# level-shifter-v0_1.net
KiCad netlist of a schematic drawn in EAGLE
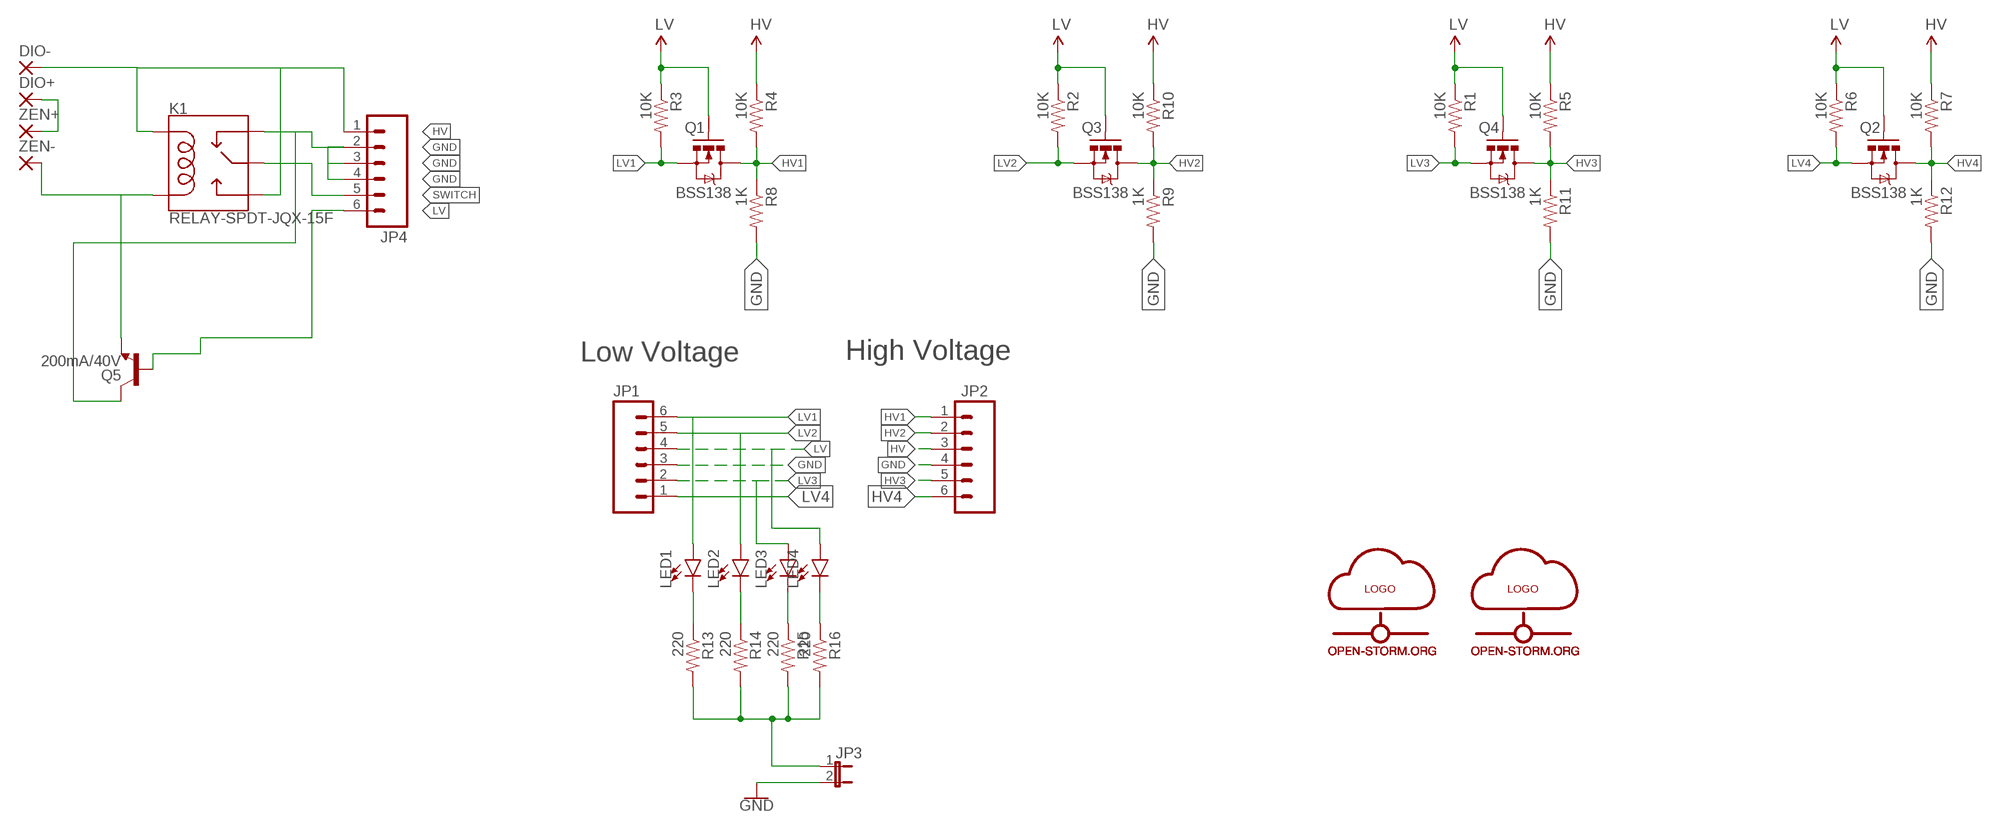
[diagram p0: schematic, sheet 1]

(export (version "E")
  (design (tool "Eeschema 10.0.6"))
  (components
    (comp (ref "DIO+")
      (value "2,15/1,0")
      (footprint "eagle-import:2,15_1,0")
      (libsource (lib "eagle-import") (part "2,15/1,0"))
    )
    (comp (ref "DIO-")
      (value "2,15/1,0")
      (footprint "eagle-import:2,15_1,0")
      (libsource (lib "eagle-import") (part "2,15/1,0"))
    )
    (comp (ref "JP1")
      (value "M06SIP")
      (footprint "eagle-import:1X06")
      (libsource (lib "eagle-import") (part "M06SIP"))
    )
    (comp (ref "JP2")
      (value "M06SIP")
      (footprint "eagle-import:1X06")
      (libsource (lib "eagle-import") (part "M06SIP"))
    )
    (comp (ref "JP3")
      (value "JUMPER-2PTH")
      (footprint "eagle-import:1X02")
      (libsource (lib "eagle-import") (part "JUMPER-2PTH"))
    )
    (comp (ref "JP4")
      (value "M06SIP")
      (footprint "eagle-import:1X06")
      (libsource (lib "eagle-import") (part "M06SIP"))
    )
    (comp (ref "K1")
      (value "RELAY-SPDT-JQX-15F")
      (footprint "eagle-import:RELAY-T90")
      (libsource (lib "eagle-import") (part "RELAY-SPDT-JQX-15F"))
    )
    (comp (ref "LED1")
      (value "LED5MM")
      (footprint "eagle-import:LED_5MM")
      (libsource (lib "eagle-import") (part "LED5MM"))
    )
    (comp (ref "LED2")
      (value "LED5MM")
      (footprint "eagle-import:LED_5MM")
      (libsource (lib "eagle-import") (part "LED5MM"))
    )
    (comp (ref "LED3")
      (value "LED5MM")
      (footprint "eagle-import:LED_5MM")
      (libsource (lib "eagle-import") (part "LED5MM"))
    )
    (comp (ref "LED4")
      (value "LED5MM")
      (footprint "eagle-import:LED_5MM")
      (libsource (lib "eagle-import") (part "LED5MM"))
    )
    (comp (ref "Q1")
      (value "BSS138")
      (footprint "eagle-import:TO-92")
      (libsource (lib "eagle-import") (part "MOSFET-NCHANNELPTH"))
    )
    (comp (ref "Q2")
      (value "BSS138")
      (footprint "eagle-import:TO-92")
      (libsource (lib "eagle-import") (part "MOSFET-NCHANNELPTH"))
    )
    (comp (ref "Q3")
      (value "BSS138")
      (footprint "eagle-import:TO-92")
      (libsource (lib "eagle-import") (part "MOSFET-NCHANNELPTH"))
    )
    (comp (ref "Q4")
      (value "BSS138")
      (footprint "eagle-import:TO-92")
      (libsource (lib "eagle-import") (part "MOSFET-NCHANNELPTH"))
    )
    (comp (ref "Q5")
      (value "200mA/40V")
      (footprint "eagle-import:TO-92")
      (libsource (lib "eagle-import") (part "TRANS_NPN-2N3904"))
    )
    (comp (ref "R1")
      (value "10K")
      (footprint "eagle-import:AXIAL-0.4")
      (libsource (lib "eagle-import") (part "RESISTORPTH-1/4W"))
    )
    (comp (ref "R2")
      (value "10K")
      (footprint "eagle-import:AXIAL-0.4")
      (libsource (lib "eagle-import") (part "RESISTORPTH-1/4W"))
    )
    (comp (ref "R3")
      (value "10K")
      (footprint "eagle-import:AXIAL-0.4")
      (libsource (lib "eagle-import") (part "RESISTORPTH-1/4W"))
    )
    (comp (ref "R4")
      (value "10K")
      (footprint "eagle-import:AXIAL-0.4")
      (libsource (lib "eagle-import") (part "RESISTORPTH-1/4W"))
    )
    (comp (ref "R5")
      (value "10K")
      (footprint "eagle-import:AXIAL-0.4")
      (libsource (lib "eagle-import") (part "RESISTORPTH-1/4W"))
    )
    (comp (ref "R6")
      (value "10K")
      (footprint "eagle-import:AXIAL-0.4")
      (libsource (lib "eagle-import") (part "RESISTORPTH-1/4W"))
    )
    (comp (ref "R7")
      (value "10K")
      (footprint "eagle-import:AXIAL-0.4")
      (libsource (lib "eagle-import") (part "RESISTORPTH-1/4W"))
    )
    (comp (ref "R8")
      (value "1K")
      (footprint "eagle-import:AXIAL-0.4")
      (libsource (lib "eagle-import") (part "RESISTORPTH-1/4W"))
    )
    (comp (ref "R9")
      (value "1K")
      (footprint "eagle-import:AXIAL-0.4")
      (libsource (lib "eagle-import") (part "RESISTORPTH-1/4W"))
    )
    (comp (ref "R10")
      (value "10K")
      (footprint "eagle-import:AXIAL-0.4")
      (libsource (lib "eagle-import") (part "RESISTORPTH-1/4W"))
    )
    (comp (ref "R11")
      (value "1K")
      (footprint "eagle-import:AXIAL-0.4")
      (libsource (lib "eagle-import") (part "RESISTORPTH-1/4W"))
    )
    (comp (ref "R12")
      (value "1K")
      (footprint "eagle-import:AXIAL-0.4")
      (libsource (lib "eagle-import") (part "RESISTORPTH-1/4W"))
    )
    (comp (ref "R13")
      (value "220")
      (footprint "eagle-import:AXIAL-0.4")
      (libsource (lib "eagle-import") (part "RESISTORPTH-1/4W"))
    )
    (comp (ref "R14")
      (value "220")
      (footprint "eagle-import:AXIAL-0.4")
      (libsource (lib "eagle-import") (part "RESISTORPTH-1/4W"))
    )
    (comp (ref "R15")
      (value "220")
      (footprint "eagle-import:AXIAL-0.4")
      (libsource (lib "eagle-import") (part "RESISTORPTH-1/4W"))
    )
    (comp (ref "R16")
      (value "220")
      (footprint "eagle-import:AXIAL-0.4")
      (libsource (lib "eagle-import") (part "RESISTORPTH-1/4W"))
    )
    (comp (ref "U$1")
      (value "OPEN-STORM-LOGO")
      (footprint "eagle-import:OPEN-STORM-LOGO")
      (libsource (lib "eagle-import") (part "OPEN-STORM-LOGO"))
    )
    (comp (ref "U$2")
      (value "OPEN-STORM-LOGO-SMALL")
      (footprint "eagle-import:OPEN-STORM-LOGO-SMALL")
      (libsource (lib "eagle-import") (part "OPEN-STORM-LOGO-SMALL"))
    )
    (comp (ref "ZEN+")
      (value "2,15/1,0")
      (footprint "eagle-import:2,15_1,0")
      (libsource (lib "eagle-import") (part "2,15/1,0"))
    )
    (comp (ref "ZEN-")
      (value "2,15/1,0")
      (footprint "eagle-import:2,15_1,0")
      (libsource (lib "eagle-import") (part "2,15/1,0"))
    )
  )
  (nets
    (net (code "1") (name "GND") (class "Default")
      (node (ref "JP1") (pin "3") (pinfunction "3_3") (pintype "passive"))
      (node (ref "JP2") (pin "4") (pinfunction "4_4") (pintype "passive"))
      (node (ref "JP3") (pin "2") (pinfunction "2_2") (pintype "passive"))
      (node (ref "JP4") (pin "2") (pinfunction "2_2") (pintype "passive"))
      (node (ref "JP4") (pin "3") (pinfunction "3_3") (pintype "passive"))
      (node (ref "JP4") (pin "4") (pinfunction "4_4") (pintype "passive"))
      (node (ref "K1") (pin "NC") (pinfunction "NC_NC") (pintype "bidirectional"))
      (node (ref "Q5") (pin "3") (pinfunction "C_3") (pintype "passive"))
      (node (ref "R11") (pin "P$2") (pinfunction "2_P$2") (pintype "passive"))
      (node (ref "R12") (pin "P$2") (pinfunction "2_P$2") (pintype "passive"))
      (node (ref "R8") (pin "P$2") (pinfunction "2_P$2") (pintype "passive"))
      (node (ref "R9") (pin "P$2") (pinfunction "2_P$2") (pintype "passive"))
    )
    (net (code "2") (name "HV") (class "Default")
      (node (ref "DIO-") (pin "1") (pinfunction "P_1") (pintype "passive"))
      (node (ref "JP2") (pin "3") (pinfunction "3_3") (pintype "passive"))
      (node (ref "JP4") (pin "1") (pinfunction "1_1") (pintype "passive"))
      (node (ref "K1") (pin "COIL1") (pinfunction "COIL1_COIL1") (pintype "bidirectional"))
      (node (ref "K1") (pin "NO") (pinfunction "NO_NO") (pintype "bidirectional"))
      (node (ref "R10") (pin "P$1") (pinfunction "1_P$1") (pintype "passive"))
      (node (ref "R4") (pin "P$1") (pinfunction "1_P$1") (pintype "passive"))
      (node (ref "R5") (pin "P$1") (pinfunction "1_P$1") (pintype "passive"))
      (node (ref "R7") (pin "P$1") (pinfunction "1_P$1") (pintype "passive"))
    )
    (net (code "3") (name "HV1") (class "Default")
      (node (ref "JP2") (pin "1") (pinfunction "1_1") (pintype "passive"))
      (node (ref "Q1") (pin "1") (pinfunction "D_1") (pintype "passive"))
      (node (ref "R4") (pin "P$2") (pinfunction "2_P$2") (pintype "passive"))
      (node (ref "R8") (pin "P$1") (pinfunction "1_P$1") (pintype "passive"))
    )
    (net (code "4") (name "HV2") (class "Default")
      (node (ref "JP2") (pin "2") (pinfunction "2_2") (pintype "passive"))
      (node (ref "Q3") (pin "1") (pinfunction "D_1") (pintype "passive"))
      (node (ref "R10") (pin "P$2") (pinfunction "2_P$2") (pintype "passive"))
      (node (ref "R9") (pin "P$1") (pinfunction "1_P$1") (pintype "passive"))
    )
    (net (code "5") (name "HV3") (class "Default")
      (node (ref "JP2") (pin "5") (pinfunction "5_5") (pintype "passive"))
      (node (ref "Q4") (pin "1") (pinfunction "D_1") (pintype "passive"))
      (node (ref "R11") (pin "P$1") (pinfunction "1_P$1") (pintype "passive"))
      (node (ref "R5") (pin "P$2") (pinfunction "2_P$2") (pintype "passive"))
    )
    (net (code "6") (name "HV4") (class "Default")
      (node (ref "JP2") (pin "6") (pinfunction "6_6") (pintype "passive"))
      (node (ref "Q2") (pin "1") (pinfunction "D_1") (pintype "passive"))
      (node (ref "R12") (pin "P$1") (pinfunction "1_P$1") (pintype "passive"))
      (node (ref "R7") (pin "P$2") (pinfunction "2_P$2") (pintype "passive"))
    )
    (net (code "7") (name "LV") (class "Default")
      (node (ref "JP1") (pin "4") (pinfunction "4_4") (pintype "passive"))
      (node (ref "JP4") (pin "6") (pinfunction "6_6") (pintype "passive"))
      (node (ref "LED4") (pin "A") (pinfunction "A_A") (pintype "passive"))
      (node (ref "Q1") (pin "3") (pinfunction "G_3") (pintype "passive"))
      (node (ref "Q2") (pin "3") (pinfunction "G_3") (pintype "passive"))
      (node (ref "Q3") (pin "3") (pinfunction "G_3") (pintype "passive"))
      (node (ref "Q4") (pin "3") (pinfunction "G_3") (pintype "passive"))
      (node (ref "Q5") (pin "2") (pinfunction "B_2") (pintype "passive"))
      (node (ref "R1") (pin "P$1") (pinfunction "1_P$1") (pintype "passive"))
      (node (ref "R2") (pin "P$1") (pinfunction "1_P$1") (pintype "passive"))
      (node (ref "R3") (pin "P$1") (pinfunction "1_P$1") (pintype "passive"))
      (node (ref "R6") (pin "P$1") (pinfunction "1_P$1") (pintype "passive"))
    )
    (net (code "8") (name "LV1") (class "Default")
      (node (ref "JP1") (pin "6") (pinfunction "6_6") (pintype "passive"))
      (node (ref "LED1") (pin "A") (pinfunction "A_A") (pintype "passive"))
      (node (ref "Q1") (pin "2") (pinfunction "S_2") (pintype "passive"))
      (node (ref "R3") (pin "P$2") (pinfunction "2_P$2") (pintype "passive"))
    )
    (net (code "9") (name "LV2") (class "Default")
      (node (ref "JP1") (pin "5") (pinfunction "5_5") (pintype "passive"))
      (node (ref "LED2") (pin "A") (pinfunction "A_A") (pintype "passive"))
      (node (ref "Q3") (pin "2") (pinfunction "S_2") (pintype "passive"))
      (node (ref "R2") (pin "P$2") (pinfunction "2_P$2") (pintype "passive"))
    )
    (net (code "10") (name "LV3") (class "Default")
      (node (ref "JP1") (pin "2") (pinfunction "2_2") (pintype "passive"))
      (node (ref "LED3") (pin "A") (pinfunction "A_A") (pintype "passive"))
      (node (ref "Q4") (pin "2") (pinfunction "S_2") (pintype "passive"))
      (node (ref "R1") (pin "P$2") (pinfunction "2_P$2") (pintype "passive"))
    )
    (net (code "11") (name "LV4") (class "Default")
      (node (ref "JP1") (pin "1") (pinfunction "1_1") (pintype "passive"))
      (node (ref "Q2") (pin "2") (pinfunction "S_2") (pintype "passive"))
      (node (ref "R6") (pin "P$2") (pinfunction "2_P$2") (pintype "passive"))
    )
    (net (code "12") (name "Net-(DIO+-P)") (class "Default")
      (node (ref "DIO+") (pin "1") (pinfunction "P_1") (pintype "passive"))
      (node (ref "ZEN+") (pin "1") (pinfunction "P_1") (pintype "passive"))
    )
    (net (code "13") (name "Net-(LED1-C)") (class "Default")
      (node (ref "LED1") (pin "K") (pinfunction "C_K") (pintype "passive"))
      (node (ref "R13") (pin "P$1") (pinfunction "1_P$1") (pintype "passive"))
    )
    (net (code "14") (name "Net-(LED2-C)") (class "Default")
      (node (ref "LED2") (pin "K") (pinfunction "C_K") (pintype "passive"))
      (node (ref "R14") (pin "P$1") (pinfunction "1_P$1") (pintype "passive"))
    )
    (net (code "15") (name "Net-(LED3-C)") (class "Default")
      (node (ref "LED3") (pin "K") (pinfunction "C_K") (pintype "passive"))
      (node (ref "R15") (pin "P$1") (pinfunction "1_P$1") (pintype "passive"))
    )
    (net (code "16") (name "Net-(LED4-C)") (class "Default")
      (node (ref "LED4") (pin "K") (pinfunction "C_K") (pintype "passive"))
      (node (ref "R16") (pin "P$1") (pinfunction "1_P$1") (pintype "passive"))
    )
    (net (code "17") (name "Net-(Q5-E)") (class "Default")
      (node (ref "K1") (pin "COIL2") (pinfunction "COIL2_COIL2") (pintype "bidirectional"))
      (node (ref "Q5") (pin "1") (pinfunction "E_1") (pintype "passive"))
      (node (ref "ZEN-") (pin "1") (pinfunction "P_1") (pintype "passive"))
    )
    (net (code "18") (name "Net-(R13-2)") (class "Default")
      (node (ref "JP3") (pin "1") (pinfunction "1_1") (pintype "passive"))
      (node (ref "R13") (pin "P$2") (pinfunction "2_P$2") (pintype "passive"))
      (node (ref "R14") (pin "P$2") (pinfunction "2_P$2") (pintype "passive"))
      (node (ref "R15") (pin "P$2") (pinfunction "2_P$2") (pintype "passive"))
      (node (ref "R16") (pin "P$2") (pinfunction "2_P$2") (pintype "passive"))
    )
    (net (code "19") (name "SWITCH") (class "Default")
      (node (ref "JP4") (pin "5") (pinfunction "5_5") (pintype "passive"))
      (node (ref "K1") (pin "MAIN") (pinfunction "MAIN_MAIN") (pintype "bidirectional"))
    )
  )
)
